# AD9244.net
KiCad netlist of a schematic drawn in Altium Designer
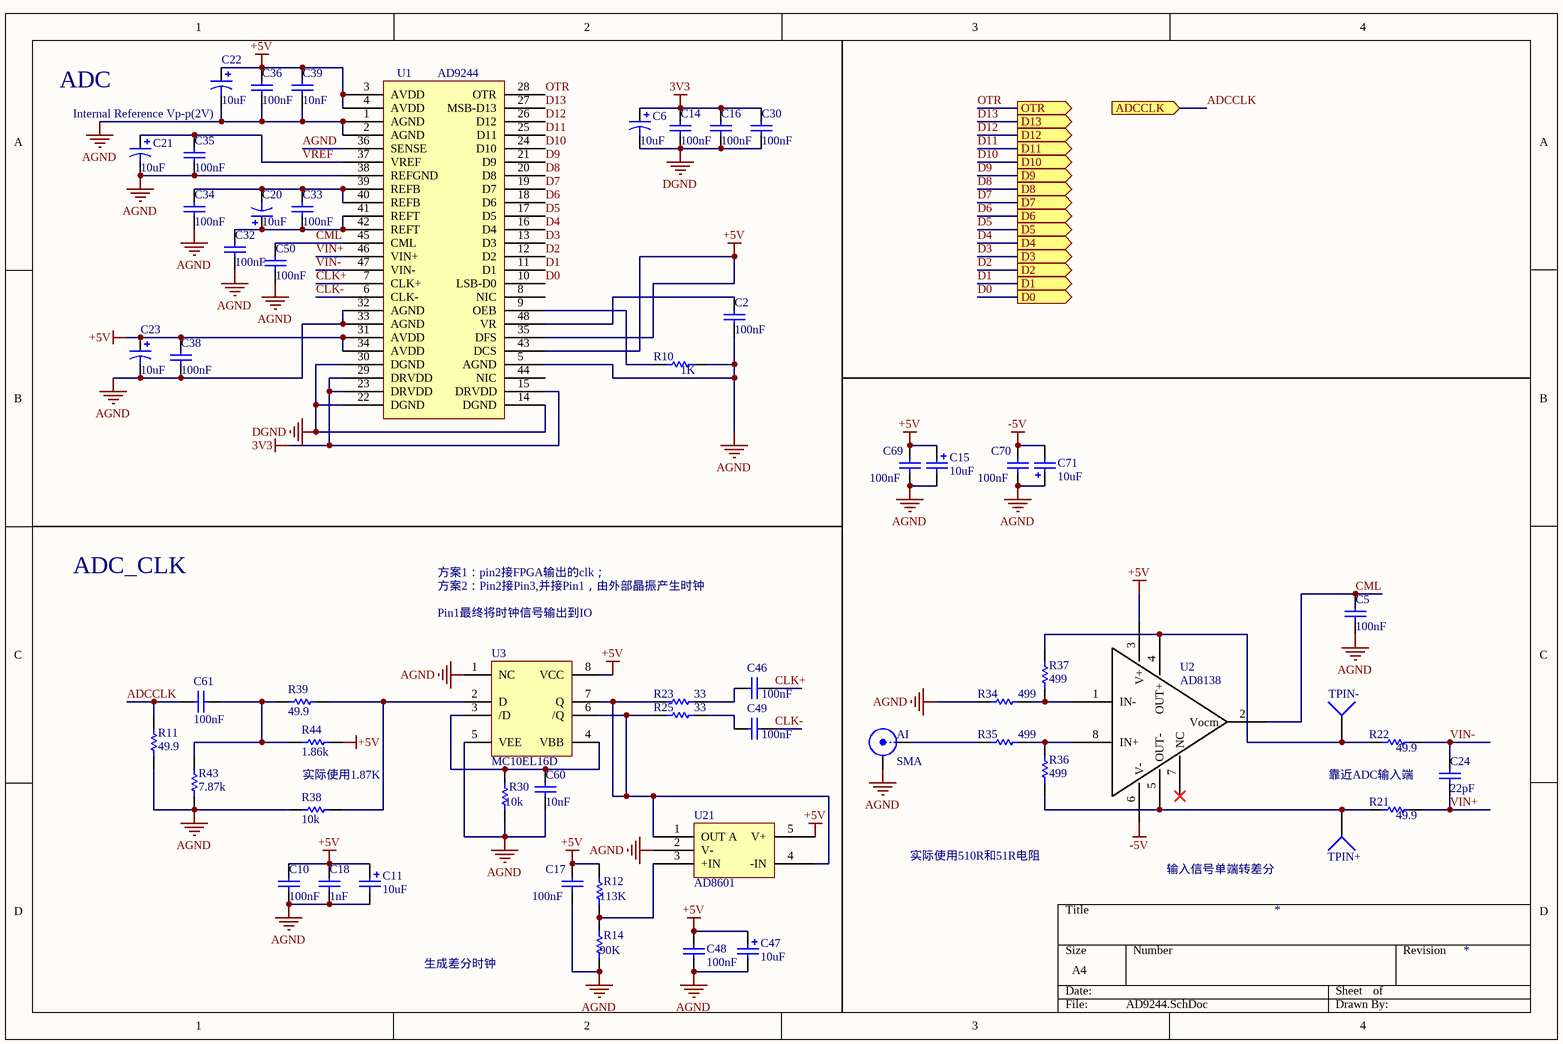
[diagram p0: AD9244.SchDoc]

(export (version "E")
  (design (tool "Eeschema 10.0.6"))
  (components
    (comp (ref "AI")
      (value "SMA")
      (footprint "SMA_SMT")
      (description "BNC Elbow Connector")
      (fields (field (name "PUBLISHER") "Altium Limited"))
      (libsource (lib "Miscellaneous Connectors") (part "BNC"))
    )
    (comp (ref "C2")
      (value "100nF")
      (footprint "BinFeng:0603")
      (description "Capacitor (Semiconductor SIM Model)")
      (fields (field (name "PUBLISHER") "Altium Limited"))
      (libsource (lib "Miscellaneous Devices") (part "Cap Semi"))
    )
    (comp (ref "C5")
      (value "100nF")
      (footprint "BinFeng:0603")
      (description "Capacitor (Semiconductor SIM Model)")
      (fields (field (name "PUBLISHER") "Altium Limited"))
      (libsource (lib "Miscellaneous Devices") (part "Cap Semi"))
    )
    (comp (ref "C6")
      (value "10uF")
      (footprint "1206")
      (description "Polarized Capacitor (Surface Mount)")
      (fields (field (name "Comment") "10uF_pol") (field (name "PUBLISHER") "Altium Limited"))
      (libsource (lib "Miscellaneous Devices") (part "Cap Pol3"))
    )
    (comp (ref "C10")
      (value "100nF")
      (footprint "BinFeng:0603")
      (description "Capacitor (Semiconductor SIM Model)")
      (fields (field (name "PUBLISHER") "Altium Limited"))
      (libsource (lib "Miscellaneous Devices") (part "Cap Semi"))
    )
    (comp (ref "C11")
      (value "10uF")
      (footprint "3216")
      (description "Polarized Capacitor (Axial)")
      (fields (field (name "PUBLISHER") "Altium Limited"))
      (libsource (lib "Miscellaneous Devices") (part "Cap Pol2"))
    )
    (comp (ref "C14")
      (value "100nF")
      (footprint "BinFeng:0603")
      (description "Capacitor (Semiconductor SIM Model)")
      (fields (field (name "PUBLISHER") "Altium Limited"))
      (libsource (lib "Miscellaneous Devices") (part "Cap Semi"))
    )
    (comp (ref "C15")
      (value "10uF")
      (footprint "3216")
      (description "Polarized Capacitor (Axial)")
      (fields (field (name "PUBLISHER") "Altium Limited"))
      (libsource (lib "Miscellaneous Devices") (part "Cap Pol2"))
    )
    (comp (ref "C16")
      (value "100nF")
      (footprint "BinFeng:0603")
      (description "Capacitor (Semiconductor SIM Model)")
      (fields (field (name "PUBLISHER") "Altium Limited"))
      (libsource (lib "Miscellaneous Devices") (part "Cap Semi"))
    )
    (comp (ref "C17")
      (value "100nF")
      (footprint "BinFeng:0603")
      (description "Capacitor (Semiconductor SIM Model)")
      (fields (field (name "PUBLISHER") "Altium Limited"))
      (libsource (lib "Miscellaneous Devices") (part "Cap Semi"))
    )
    (comp (ref "C18")
      (value "1nF")
      (footprint "BinFeng:0603")
      (description "Capacitor (Semiconductor SIM Model)")
      (fields (field (name "PUBLISHER") "Altium Limited"))
      (libsource (lib "Miscellaneous Devices") (part "Cap Semi"))
    )
    (comp (ref "C20")
      (value "10uF")
      (footprint "1206")
      (description "Polarized Capacitor (Surface Mount)")
      (fields (field (name "Comment") "10uF_pol") (field (name "PUBLISHER") "Altium Limited"))
      (libsource (lib "Miscellaneous Devices") (part "Cap Pol3"))
    )
    (comp (ref "C21")
      (value "10uF")
      (footprint "1206")
      (description "Polarized Capacitor (Surface Mount)")
      (fields (field (name "Comment") "10uF_pol") (field (name "PUBLISHER") "Altium Limited"))
      (libsource (lib "Miscellaneous Devices") (part "Cap Pol3"))
    )
    (comp (ref "C22")
      (value "10uF")
      (footprint "1206")
      (description "Polarized Capacitor (Surface Mount)")
      (fields (field (name "Comment") "10uF_pol") (field (name "PUBLISHER") "Altium Limited"))
      (libsource (lib "Miscellaneous Devices") (part "Cap Pol3"))
    )
    (comp (ref "C23")
      (value "10uF")
      (footprint "1206")
      (description "Polarized Capacitor (Surface Mount)")
      (fields (field (name "Comment") "10uF_pol") (field (name "PUBLISHER") "Altium Limited"))
      (libsource (lib "Miscellaneous Devices") (part "Cap Pol3"))
    )
    (comp (ref "C24")
      (value "22pF")
      (footprint "BinFeng:0603")
      (description "Capacitor (Semiconductor SIM Model)")
      (fields (field (name "PUBLISHER") "Altium Limited"))
      (libsource (lib "Miscellaneous Devices") (part "Cap Semi"))
    )
    (comp (ref "C30")
      (value "100nF")
      (footprint "BinFeng:0603")
      (description "Capacitor (Semiconductor SIM Model)")
      (fields (field (name "PUBLISHER") "Altium Limited"))
      (libsource (lib "Miscellaneous Devices") (part "Cap Semi"))
    )
    (comp (ref "C32")
      (value "100nF")
      (footprint "BinFeng:0603")
      (description "Capacitor (Semiconductor SIM Model)")
      (fields (field (name "PUBLISHER") "Altium Limited"))
      (libsource (lib "Miscellaneous Devices") (part "Cap Semi"))
    )
    (comp (ref "C33")
      (value "100nF")
      (footprint "BinFeng:0603")
      (description "Capacitor (Semiconductor SIM Model)")
      (fields (field (name "PUBLISHER") "Altium Limited"))
      (libsource (lib "Miscellaneous Devices") (part "Cap Semi"))
    )
    (comp (ref "C34")
      (value "100nF")
      (footprint "BinFeng:0603")
      (description "Capacitor (Semiconductor SIM Model)")
      (fields (field (name "PUBLISHER") "Altium Limited"))
      (libsource (lib "Miscellaneous Devices") (part "Cap Semi"))
    )
    (comp (ref "C35")
      (value "100nF")
      (footprint "BinFeng:0603")
      (description "Capacitor (Semiconductor SIM Model)")
      (fields (field (name "PUBLISHER") "Altium Limited"))
      (libsource (lib "Miscellaneous Devices") (part "Cap Semi"))
    )
    (comp (ref "C36")
      (value "100nF")
      (footprint "BinFeng:0603")
      (description "Capacitor (Semiconductor SIM Model)")
      (fields (field (name "PUBLISHER") "Altium Limited"))
      (libsource (lib "Miscellaneous Devices") (part "Cap Semi"))
    )
    (comp (ref "C38")
      (value "100nF")
      (footprint "BinFeng:0603")
      (description "Capacitor (Semiconductor SIM Model)")
      (fields (field (name "PUBLISHER") "Altium Limited"))
      (libsource (lib "Miscellaneous Devices") (part "Cap Semi"))
    )
    (comp (ref "C39")
      (value "10nF")
      (footprint "BinFeng:0603")
      (description "Capacitor (Semiconductor SIM Model)")
      (fields (field (name "Comment") "100nF") (field (name "PUBLISHER") "Altium Limited"))
      (libsource (lib "Miscellaneous Devices") (part "Cap Semi"))
    )
    (comp (ref "C46")
      (value "100nF")
      (footprint "BinFeng:0603")
      (description "Capacitor (Semiconductor SIM Model)")
      (fields (field (name "PUBLISHER") "Altium Limited"))
      (libsource (lib "Miscellaneous Devices") (part "Cap Semi"))
    )
    (comp (ref "C47")
      (value "10uF")
      (footprint "3216")
      (description "Polarized Capacitor (Axial)")
      (fields (field (name "PUBLISHER") "Altium Limited"))
      (libsource (lib "Miscellaneous Devices") (part "Cap Pol2"))
    )
    (comp (ref "C48")
      (value "100nF")
      (footprint "BinFeng:0603")
      (description "Capacitor (Semiconductor SIM Model)")
      (fields (field (name "PUBLISHER") "Altium Limited"))
      (libsource (lib "Miscellaneous Devices") (part "Cap Semi"))
    )
    (comp (ref "C49")
      (value "100nF")
      (footprint "BinFeng:0603")
      (description "Capacitor (Semiconductor SIM Model)")
      (fields (field (name "PUBLISHER") "Altium Limited"))
      (libsource (lib "Miscellaneous Devices") (part "Cap Semi"))
    )
    (comp (ref "C50")
      (value "100nF")
      (footprint "BinFeng:0603")
      (description "Capacitor (Semiconductor SIM Model)")
      (fields (field (name "PUBLISHER") "Altium Limited"))
      (libsource (lib "Miscellaneous Devices") (part "Cap Semi"))
    )
    (comp (ref "C60")
      (value "10nF")
      (footprint "BinFeng:0603")
      (description "Capacitor (Semiconductor SIM Model)")
      (fields (field (name "PUBLISHER") "Altium Limited"))
      (libsource (lib "Miscellaneous Devices") (part "Cap Semi"))
    )
    (comp (ref "C61")
      (value "100nF")
      (footprint "BinFeng:0603")
      (description "Capacitor (Semiconductor SIM Model)")
      (fields (field (name "PUBLISHER") "Altium Limited"))
      (libsource (lib "Miscellaneous Devices") (part "Cap Semi"))
    )
    (comp (ref "C69")
      (value "100nF")
      (footprint "BinFeng:0603")
      (description "Capacitor (Semiconductor SIM Model)")
      (fields (field (name "PUBLISHER") "Altium Limited"))
      (libsource (lib "Miscellaneous Devices") (part "Cap Semi"))
    )
    (comp (ref "C70")
      (value "100nF")
      (footprint "BinFeng:0603")
      (description "Capacitor (Semiconductor SIM Model)")
      (fields (field (name "PUBLISHER") "Altium Limited"))
      (libsource (lib "Miscellaneous Devices") (part "Cap Semi"))
    )
    (comp (ref "C71")
      (value "10uF")
      (footprint "3216")
      (description "Polarized Capacitor (Axial)")
      (fields (field (name "PUBLISHER") "Altium Limited"))
      (libsource (lib "Miscellaneous Devices") (part "Cap Pol2"))
    )
    (comp (ref "R10")
      (value "1K")
      (footprint "BinFeng:0603")
      (description "Resistor")
      (fields (field (name "Comment") "1k") (field (name "PUBLISHER") "Altium Limited"))
      (libsource (lib "Miscellaneous Devices") (part "Res1"))
    )
    (comp (ref "R11")
      (value "49.9")
      (footprint "BinFeng:0603")
      (description "Resistor")
      (fields (field (name "PUBLISHER") "Altium Limited"))
      (libsource (lib "Miscellaneous Devices") (part "Res1"))
    )
    (comp (ref "R12")
      (value "113K")
      (footprint "BinFeng:0603")
      (description "Resistor")
      (fields (field (name "PUBLISHER") "Altium Limited"))
      (libsource (lib "Miscellaneous Devices") (part "Res1"))
    )
    (comp (ref "R14")
      (value "90K")
      (footprint "BinFeng:0603")
      (description "Resistor")
      (fields (field (name "PUBLISHER") "Altium Limited"))
      (libsource (lib "Miscellaneous Devices") (part "Res1"))
    )
    (comp (ref "R21")
      (value "49.9")
      (footprint "BinFeng:0603")
      (description "Resistor")
      (fields (field (name "PUBLISHER") "Altium Limited"))
      (libsource (lib "Miscellaneous Devices") (part "Res1"))
    )
    (comp (ref "R22")
      (value "49.9")
      (footprint "BinFeng:0603")
      (description "Resistor")
      (fields (field (name "PUBLISHER") "Altium Limited"))
      (libsource (lib "Miscellaneous Devices") (part "Res1"))
    )
    (comp (ref "R23")
      (value "33")
      (footprint "BinFeng:0603")
      (description "Resistor")
      (fields (field (name "PUBLISHER") "Altium Limited"))
      (libsource (lib "Miscellaneous Devices") (part "Res1"))
    )
    (comp (ref "R25")
      (value "33")
      (footprint "BinFeng:0603")
      (description "Resistor")
      (fields (field (name "PUBLISHER") "Altium Limited"))
      (libsource (lib "Miscellaneous Devices") (part "Res1"))
    )
    (comp (ref "R30")
      (value "10k")
      (footprint "BinFeng:0603")
      (description "Resistor")
      (fields (field (name "PUBLISHER") "Altium Limited"))
      (libsource (lib "Miscellaneous Devices") (part "Res1"))
    )
    (comp (ref "R34")
      (value "499")
      (footprint "BinFeng:0603")
      (description "Resistor")
      (fields (field (name "PUBLISHER") "Altium Limited"))
      (libsource (lib "Miscellaneous Devices") (part "Res1"))
    )
    (comp (ref "R35")
      (value "499")
      (footprint "BinFeng:0603")
      (description "Resistor")
      (fields (field (name "PUBLISHER") "Altium Limited"))
      (libsource (lib "Miscellaneous Devices") (part "Res1"))
    )
    (comp (ref "R36")
      (value "499")
      (footprint "BinFeng:0603")
      (description "Resistor")
      (fields (field (name "PUBLISHER") "Altium Limited"))
      (libsource (lib "Miscellaneous Devices") (part "Res1"))
    )
    (comp (ref "R37")
      (value "499")
      (footprint "BinFeng:0603")
      (description "Resistor")
      (fields (field (name "PUBLISHER") "Altium Limited"))
      (libsource (lib "Miscellaneous Devices") (part "Res1"))
    )
    (comp (ref "R38")
      (value "10k")
      (footprint "BinFeng:0603")
      (description "Resistor")
      (fields (field (name "PUBLISHER") "Altium Limited"))
      (libsource (lib "Miscellaneous Devices") (part "Res1"))
    )
    (comp (ref "R39")
      (value "49.9")
      (footprint "BinFeng:0603")
      (description "Resistor")
      (fields (field (name "Comment") "49。9") (field (name "PUBLISHER") "Altium Limited"))
      (libsource (lib "Miscellaneous Devices") (part "Res1"))
    )
    (comp (ref "R43")
      (value "7.87k")
      (footprint "BinFeng:0603")
      (description "Resistor")
      (fields (field (name "PUBLISHER") "Altium Limited"))
      (libsource (lib "Miscellaneous Devices") (part "Res1"))
    )
    (comp (ref "R44")
      (value "1.86k")
      (footprint "BinFeng:0603")
      (description "Resistor")
      (fields (field (name "PUBLISHER") "Altium Limited"))
      (libsource (lib "Miscellaneous Devices") (part "Res1"))
    )
    (comp (ref "TPIN+")
      (value "TPIN+")
      (footprint "PIN1")
      (description "Socket")
      (fields (field (name "PUBLISHER") "Altium Limited"))
      (libsource (lib "Miscellaneous Connectors") (part "Socket"))
    )
    (comp (ref "TPIN-")
      (value "TPIN-")
      (footprint "PIN1")
      (description "Socket")
      (fields (field (name "PUBLISHER") "Altium Limited"))
      (libsource (lib "Miscellaneous Connectors") (part "Socket"))
    )
    (comp (ref "U1") (value "AD9244") (libsource (lib "LEDx4") (part "DSx4")))
    (comp (ref "U2") (value "AD8138") (footprint "SO-8N") (libsource (lib "BinFeng_IC") (part "AD8138")))
    (comp (ref "U3") (value "MC10EL16D") (footprint "SO-8") (libsource (lib "BinFeng_IC") (part "MC10EL16D")))
    (comp (ref "U21")
      (value "AD8601")
      (footprint "SOT23-5")
      (description "Precision CMOS, Single Supply, Rail to Rail, Windband Operational Amplifiers")
      (libsource (lib "BinFeng_IC") (part "AD8601"))
    )
  )
  (nets
    (net (code "1") (name "+5V") (class "Default")
      (node (ref "C10") (pin "1") (pinfunction "1_1") (pintype "passive"))
      (node (ref "C11") (pin "1") (pinfunction "1_1") (pintype "passive"))
      (node (ref "C15") (pin "1") (pinfunction "1_1") (pintype "passive"))
      (node (ref "C17") (pin "1") (pinfunction "1_1") (pintype "passive"))
      (node (ref "C18") (pin "1") (pinfunction "1_1") (pintype "passive"))
      (node (ref "C22") (pin "1") (pinfunction "1_1") (pintype "passive"))
      (node (ref "C23") (pin "1") (pinfunction "1_1") (pintype "passive"))
      (node (ref "C36") (pin "1") (pinfunction "1_1") (pintype "passive"))
      (node (ref "C38") (pin "1") (pinfunction "1_1") (pintype "passive"))
      (node (ref "C39") (pin "1") (pinfunction "1_1") (pintype "passive"))
      (node (ref "C47") (pin "1") (pinfunction "1_1") (pintype "passive"))
      (node (ref "C48") (pin "2") (pinfunction "2_2") (pintype "passive"))
      (node (ref "C69") (pin "2") (pinfunction "2_2") (pintype "passive"))
      (node (ref "R12") (pin "1") (pinfunction "1_1") (pintype "passive"))
      (node (ref "R44") (pin "1") (pinfunction "1_1") (pintype "passive"))
      (node (ref "U1") (pin "3") (pinfunction "AVDD_3") (pintype "passive"))
      (node (ref "U1") (pin "31") (pinfunction "AVDD_31") (pintype "passive"))
      (node (ref "U1") (pin "34") (pinfunction "AVDD_34") (pintype "passive"))
      (node (ref "U1") (pin "35") (pinfunction "DFS_35") (pintype "passive"))
      (node (ref "U1") (pin "4") (pinfunction "AVDD_4") (pintype "passive"))
      (node (ref "U1") (pin "43") (pinfunction "DCS_43") (pintype "passive"))
      (node (ref "U2") (pin "3") (pinfunction "V+_3") (pintype "passive"))
      (node (ref "U21") (pin "5") (pinfunction "V+_5") (pintype "passive"))
      (node (ref "U3") (pin "8") (pinfunction "VCC_8") (pintype "passive"))
    )
    (net (code "2") (name "-5V") (class "Default")
      (node (ref "C70") (pin "2") (pinfunction "2_2") (pintype "passive"))
      (node (ref "C71") (pin "2") (pinfunction "2_2") (pintype "passive"))
      (node (ref "U2") (pin "6") (pinfunction "V-_6") (pintype "passive"))
    )
    (net (code "3") (name "/ADCCLK") (class "Default")
      (node (ref "C61") (pin "1") (pinfunction "1_1") (pintype "passive"))
      (node (ref "R11") (pin "2") (pinfunction "2_2") (pintype "passive"))
    )
    (net (code "4") (name "/CLK+") (class "Default")
      (node (ref "C46") (pin "2") (pinfunction "2_2") (pintype "passive"))
      (node (ref "U1") (pin "7") (pinfunction "CLK+_7") (pintype "passive"))
    )
    (net (code "5") (name "/CLK-") (class "Default")
      (node (ref "C49") (pin "2") (pinfunction "2_2") (pintype "passive"))
      (node (ref "U1") (pin "6") (pinfunction "CLK-_6") (pintype "passive"))
    )
    (net (code "6") (name "/CML") (class "Default")
      (node (ref "C5") (pin "1") (pinfunction "1_1") (pintype "passive"))
      (node (ref "C50") (pin "1") (pinfunction "1_1") (pintype "passive"))
      (node (ref "U1") (pin "45") (pinfunction "CML_45") (pintype "passive"))
      (node (ref "U2") (pin "2") (pinfunction "Vocm_2") (pintype "passive"))
    )
    (net (code "7") (name "/D0") (class "Default")
      (node (ref "U1") (pin "10") (pinfunction "LSB-D0_10") (pintype "passive"))
    )
    (net (code "8") (name "/D1") (class "Default")
      (node (ref "U1") (pin "11") (pinfunction "D1_11") (pintype "passive"))
    )
    (net (code "9") (name "/D2") (class "Default")
      (node (ref "U1") (pin "12") (pinfunction "D2_12") (pintype "passive"))
    )
    (net (code "10") (name "/D3") (class "Default")
      (node (ref "U1") (pin "13") (pinfunction "D3_13") (pintype "passive"))
    )
    (net (code "11") (name "/D4") (class "Default")
      (node (ref "U1") (pin "16") (pinfunction "D4_16") (pintype "passive"))
    )
    (net (code "12") (name "/D5") (class "Default")
      (node (ref "U1") (pin "17") (pinfunction "D5_17") (pintype "passive"))
    )
    (net (code "13") (name "/D6") (class "Default")
      (node (ref "U1") (pin "18") (pinfunction "D6_18") (pintype "passive"))
    )
    (net (code "14") (name "/D7") (class "Default")
      (node (ref "U1") (pin "19") (pinfunction "D7_19") (pintype "passive"))
    )
    (net (code "15") (name "/D8") (class "Default")
      (node (ref "U1") (pin "20") (pinfunction "D8_20") (pintype "passive"))
    )
    (net (code "16") (name "/D9") (class "Default")
      (node (ref "U1") (pin "21") (pinfunction "D9_21") (pintype "passive"))
    )
    (net (code "17") (name "/D10") (class "Default")
      (node (ref "U1") (pin "24") (pinfunction "D10_24") (pintype "passive"))
    )
    (net (code "18") (name "/D11") (class "Default")
      (node (ref "U1") (pin "25") (pinfunction "D11_25") (pintype "passive"))
    )
    (net (code "19") (name "/D12") (class "Default")
      (node (ref "U1") (pin "26") (pinfunction "D12_26") (pintype "passive"))
    )
    (net (code "20") (name "/D13") (class "Default")
      (node (ref "U1") (pin "27") (pinfunction "MSB-D13_27") (pintype "passive"))
    )
    (net (code "21") (name "/OTR") (class "Default")
      (node (ref "U1") (pin "28") (pinfunction "OTR_28") (pintype "passive"))
    )
    (net (code "22") (name "/VIN+") (class "Default")
      (node (ref "C24") (pin "2") (pinfunction "2_2") (pintype "passive"))
      (node (ref "R21") (pin "1") (pinfunction "1_1") (pintype "passive"))
      (node (ref "U1") (pin "46") (pinfunction "VIN+_46") (pintype "passive"))
    )
    (net (code "23") (name "/VIN-") (class "Default")
      (node (ref "C24") (pin "1") (pinfunction "1_1") (pintype "passive"))
      (node (ref "R22") (pin "1") (pinfunction "1_1") (pintype "passive"))
      (node (ref "U1") (pin "47") (pinfunction "VIN-_47") (pintype "passive"))
    )
    (net (code "24") (name "/VREF") (class "Default")
      (node (ref "C21") (pin "1") (pinfunction "1_1") (pintype "passive"))
      (node (ref "C35") (pin "1") (pinfunction "1_1") (pintype "passive"))
      (node (ref "U1") (pin "37") (pinfunction "VREF_37") (pintype "passive"))
    )
    (net (code "25") (name "3V3") (class "Default")
      (node (ref "C14") (pin "1") (pinfunction "1_1") (pintype "passive"))
      (node (ref "C16") (pin "1") (pinfunction "1_1") (pintype "passive"))
      (node (ref "C30") (pin "1") (pinfunction "1_1") (pintype "passive"))
      (node (ref "C6") (pin "1") (pinfunction "1_1") (pintype "passive"))
      (node (ref "U1") (pin "15") (pinfunction "DRVDD_15") (pintype "passive"))
      (node (ref "U1") (pin "23") (pinfunction "DRVDD_23") (pintype "passive"))
      (node (ref "U1") (pin "29") (pinfunction "DRVDD_29") (pintype "passive"))
    )
    (net (code "26") (name "AGND") (class "Default")
      (node (ref "AI") (pin "2") (pinfunction "Y_2") (pintype "passive"))
      (node (ref "C10") (pin "2") (pinfunction "2_2") (pintype "passive"))
      (node (ref "C11") (pin "2") (pinfunction "2_2") (pintype "passive"))
      (node (ref "C15") (pin "2") (pinfunction "2_2") (pintype "passive"))
      (node (ref "C17") (pin "2") (pinfunction "2_2") (pintype "passive"))
      (node (ref "C18") (pin "2") (pinfunction "2_2") (pintype "passive"))
      (node (ref "C2") (pin "2") (pinfunction "2_2") (pintype "passive"))
      (node (ref "C21") (pin "2") (pinfunction "2_2") (pintype "passive"))
      (node (ref "C22") (pin "2") (pinfunction "2_2") (pintype "passive"))
      (node (ref "C23") (pin "2") (pinfunction "2_2") (pintype "passive"))
      (node (ref "C32") (pin "2") (pinfunction "2_2") (pintype "passive"))
      (node (ref "C34") (pin "2") (pinfunction "2_2") (pintype "passive"))
      (node (ref "C35") (pin "2") (pinfunction "2_2") (pintype "passive"))
      (node (ref "C36") (pin "2") (pinfunction "2_2") (pintype "passive"))
      (node (ref "C38") (pin "2") (pinfunction "2_2") (pintype "passive"))
      (node (ref "C39") (pin "2") (pinfunction "2_2") (pintype "passive"))
      (node (ref "C47") (pin "2") (pinfunction "2_2") (pintype "passive"))
      (node (ref "C48") (pin "1") (pinfunction "1_1") (pintype "passive"))
      (node (ref "C5") (pin "2") (pinfunction "2_2") (pintype "passive"))
      (node (ref "C50") (pin "2") (pinfunction "2_2") (pintype "passive"))
      (node (ref "C60") (pin "2") (pinfunction "2_2") (pintype "passive"))
      (node (ref "C69") (pin "1") (pinfunction "1_1") (pintype "passive"))
      (node (ref "C70") (pin "1") (pinfunction "1_1") (pintype "passive"))
      (node (ref "C71") (pin "1") (pinfunction "1_1") (pintype "passive"))
      (node (ref "R10") (pin "1") (pinfunction "1_1") (pintype "passive"))
      (node (ref "R11") (pin "1") (pinfunction "1_1") (pintype "passive"))
      (node (ref "R14") (pin "2") (pinfunction "2_2") (pintype "passive"))
      (node (ref "R30") (pin "2") (pinfunction "2_2") (pintype "passive"))
      (node (ref "R34") (pin "1") (pinfunction "1_1") (pintype "passive"))
      (node (ref "R38") (pin "2") (pinfunction "2_2") (pintype "passive"))
      (node (ref "R43") (pin "1") (pinfunction "1_1") (pintype "passive"))
      (node (ref "U1") (pin "1") (pinfunction "AGND_1") (pintype "passive"))
      (node (ref "U1") (pin "2") (pinfunction "AGND_2") (pintype "passive"))
      (node (ref "U1") (pin "32") (pinfunction "AGND_32") (pintype "passive"))
      (node (ref "U1") (pin "33") (pinfunction "AGND_33") (pintype "passive"))
      (node (ref "U1") (pin "36") (pinfunction "SENSE_36") (pintype "passive"))
      (node (ref "U1") (pin "38") (pinfunction "REFGND_38") (pintype "passive"))
      (node (ref "U1") (pin "5") (pinfunction "AGND_5") (pintype "passive"))
      (node (ref "U21") (pin "2") (pinfunction "V-_2") (pintype "passive"))
      (node (ref "U3") (pin "1") (pinfunction "NC_1") (pintype "passive"))
      (node (ref "U3") (pin "5") (pinfunction "VEE_5") (pintype "passive"))
    )
    (net (code "27") (name "DGND") (class "Default")
      (node (ref "C14") (pin "2") (pinfunction "2_2") (pintype "passive"))
      (node (ref "C16") (pin "2") (pinfunction "2_2") (pintype "passive"))
      (node (ref "C30") (pin "2") (pinfunction "2_2") (pintype "passive"))
      (node (ref "C6") (pin "2") (pinfunction "2_2") (pintype "passive"))
      (node (ref "U1") (pin "14") (pinfunction "DGND_14") (pintype "passive"))
      (node (ref "U1") (pin "22") (pinfunction "DGND_22") (pintype "passive"))
      (node (ref "U1") (pin "30") (pinfunction "DGND_30") (pintype "passive"))
    )
    (net (code "28") (name "Net-(AI-X)") (class "Default")
      (node (ref "AI") (pin "1") (pinfunction "X_1") (pintype "passive"))
      (node (ref "R35") (pin "1") (pinfunction "1_1") (pintype "passive"))
    )
    (net (code "29") (name "Net-(C20-Pad1)") (class "Default")
      (node (ref "C20") (pin "1") (pinfunction "1_1") (pintype "passive"))
      (node (ref "C32") (pin "1") (pinfunction "1_1") (pintype "passive"))
      (node (ref "C33") (pin "2") (pinfunction "2_2") (pintype "passive"))
      (node (ref "U1") (pin "41") (pinfunction "REFT_41") (pintype "passive"))
      (node (ref "U1") (pin "42") (pinfunction "REFT_42") (pintype "passive"))
    )
    (net (code "30") (name "Net-(C20-Pad2)") (class "Default")
      (node (ref "C20") (pin "2") (pinfunction "2_2") (pintype "passive"))
      (node (ref "C33") (pin "1") (pinfunction "1_1") (pintype "passive"))
      (node (ref "C34") (pin "1") (pinfunction "1_1") (pintype "passive"))
      (node (ref "U1") (pin "39") (pinfunction "REFB_39") (pintype "passive"))
      (node (ref "U1") (pin "40") (pinfunction "REFB_40") (pintype "passive"))
    )
    (net (code "31") (name "Net-(C46-Pad1)") (class "Default")
      (node (ref "C46") (pin "1") (pinfunction "1_1") (pintype "passive"))
      (node (ref "R23") (pin "2") (pinfunction "2_2") (pintype "passive"))
    )
    (net (code "32") (name "Net-(C49-Pad1)") (class "Default")
      (node (ref "C49") (pin "1") (pinfunction "1_1") (pintype "passive"))
      (node (ref "R25") (pin "2") (pinfunction "2_2") (pintype "passive"))
    )
    (net (code "33") (name "Net-(C61-Pad2)") (class "Default")
      (node (ref "C61") (pin "2") (pinfunction "2_2") (pintype "passive"))
      (node (ref "R39") (pin "2") (pinfunction "2_2") (pintype "passive"))
      (node (ref "R43") (pin "2") (pinfunction "2_2") (pintype "passive"))
      (node (ref "R44") (pin "2") (pinfunction "2_2") (pintype "passive"))
    )
    (net (code "34") (name "Net-(U1-OEB)") (class "Default")
      (node (ref "R10") (pin "2") (pinfunction "2_2") (pintype "passive"))
      (node (ref "U1") (pin "9") (pinfunction "OEB_9") (pintype "passive"))
    )
    (net (code "35") (name "Net-(U1-VR)") (class "Default")
      (node (ref "C2") (pin "1") (pinfunction "1_1") (pintype "passive"))
      (node (ref "U1") (pin "48") (pinfunction "VR_48") (pintype "passive"))
    )
    (net (code "36") (name "Net-(U2-IN+)") (class "Default")
      (node (ref "R35") (pin "2") (pinfunction "2_2") (pintype "passive"))
      (node (ref "R36") (pin "2") (pinfunction "2_2") (pintype "passive"))
      (node (ref "U2") (pin "8") (pinfunction "IN+_8") (pintype "passive"))
    )
    (net (code "37") (name "Net-(U2-IN-)") (class "Default")
      (node (ref "R34") (pin "2") (pinfunction "2_2") (pintype "passive"))
      (node (ref "R37") (pin "1") (pinfunction "1_1") (pintype "passive"))
      (node (ref "U2") (pin "1") (pinfunction "IN-_1") (pintype "passive"))
    )
    (net (code "38") (name "Net-(U2-OUT+)") (class "Default")
      (node (ref "R22") (pin "2") (pinfunction "2_2") (pintype "passive"))
      (node (ref "R37") (pin "2") (pinfunction "2_2") (pintype "passive"))
      (node (ref "TPIN-") (pin "1") (pinfunction "1_1") (pintype "passive"))
      (node (ref "U2") (pin "4") (pinfunction "OUT+_4") (pintype "passive"))
    )
    (net (code "39") (name "Net-(U2-OUT-)") (class "Default")
      (node (ref "R21") (pin "2") (pinfunction "2_2") (pintype "passive"))
      (node (ref "R36") (pin "1") (pinfunction "1_1") (pintype "passive"))
      (node (ref "TPIN+") (pin "1") (pinfunction "1_1") (pintype "passive"))
      (node (ref "U2") (pin "5") (pinfunction "OUT-_5") (pintype "passive"))
    )
    (net (code "40") (name "Net-(U3-D)") (class "Default")
      (node (ref "R38") (pin "1") (pinfunction "1_1") (pintype "passive"))
      (node (ref "R39") (pin "1") (pinfunction "1_1") (pintype "passive"))
      (node (ref "U3") (pin "2") (pinfunction "D_2") (pintype "passive"))
    )
    (net (code "41") (name "Net-(U3-VBB)") (class "Default")
      (node (ref "C60") (pin "1") (pinfunction "1_1") (pintype "passive"))
      (node (ref "R30") (pin "1") (pinfunction "1_1") (pintype "passive"))
      (node (ref "U3") (pin "3") (pinfunction "/D_3") (pintype "passive"))
      (node (ref "U3") (pin "4") (pinfunction "VBB_4") (pintype "passive"))
    )
    (net (code "42") (name "Net-(U21-+IN)") (class "Default")
      (node (ref "R12") (pin "2") (pinfunction "2_2") (pintype "passive"))
      (node (ref "R14") (pin "1") (pinfunction "1_1") (pintype "passive"))
      (node (ref "U21") (pin "3") (pinfunction "+IN_3") (pintype "passive"))
    )
    (net (code "43") (name "Net-(U21--IN)") (class "Default")
      (node (ref "R23") (pin "1") (pinfunction "1_1") (pintype "passive"))
      (node (ref "R25") (pin "1") (pinfunction "1_1") (pintype "passive"))
      (node (ref "U21") (pin "1") (pinfunction "OUT_A_1") (pintype "passive"))
      (node (ref "U21") (pin "4") (pinfunction "-IN_4") (pintype "passive"))
      (node (ref "U3") (pin "6") (pinfunction "/Q_6") (pintype "passive"))
      (node (ref "U3") (pin "7") (pinfunction "Q_7") (pintype "passive"))
    )
    (net (code "44") (name "unconnected-(U1-NIC-Pad8)") (class "Default")
      (node (ref "U1") (pin "8") (pinfunction "NIC_8") (pintype "passive"))
    )
    (net (code "45") (name "unconnected-(U1-NIC-Pad44)") (class "Default")
      (node (ref "U1") (pin "44") (pinfunction "NIC_44") (pintype "passive"))
    )
    (net (code "46") (name "unconnected-(U2-NC-Pad7)") (class "Default")
      (node (ref "U2") (pin "7") (pinfunction "NC_7") (pintype "passive+no_connect"))
    )
  )
)
